# Power.net
KiCad netlist of a schematic drawn in Altium Designer
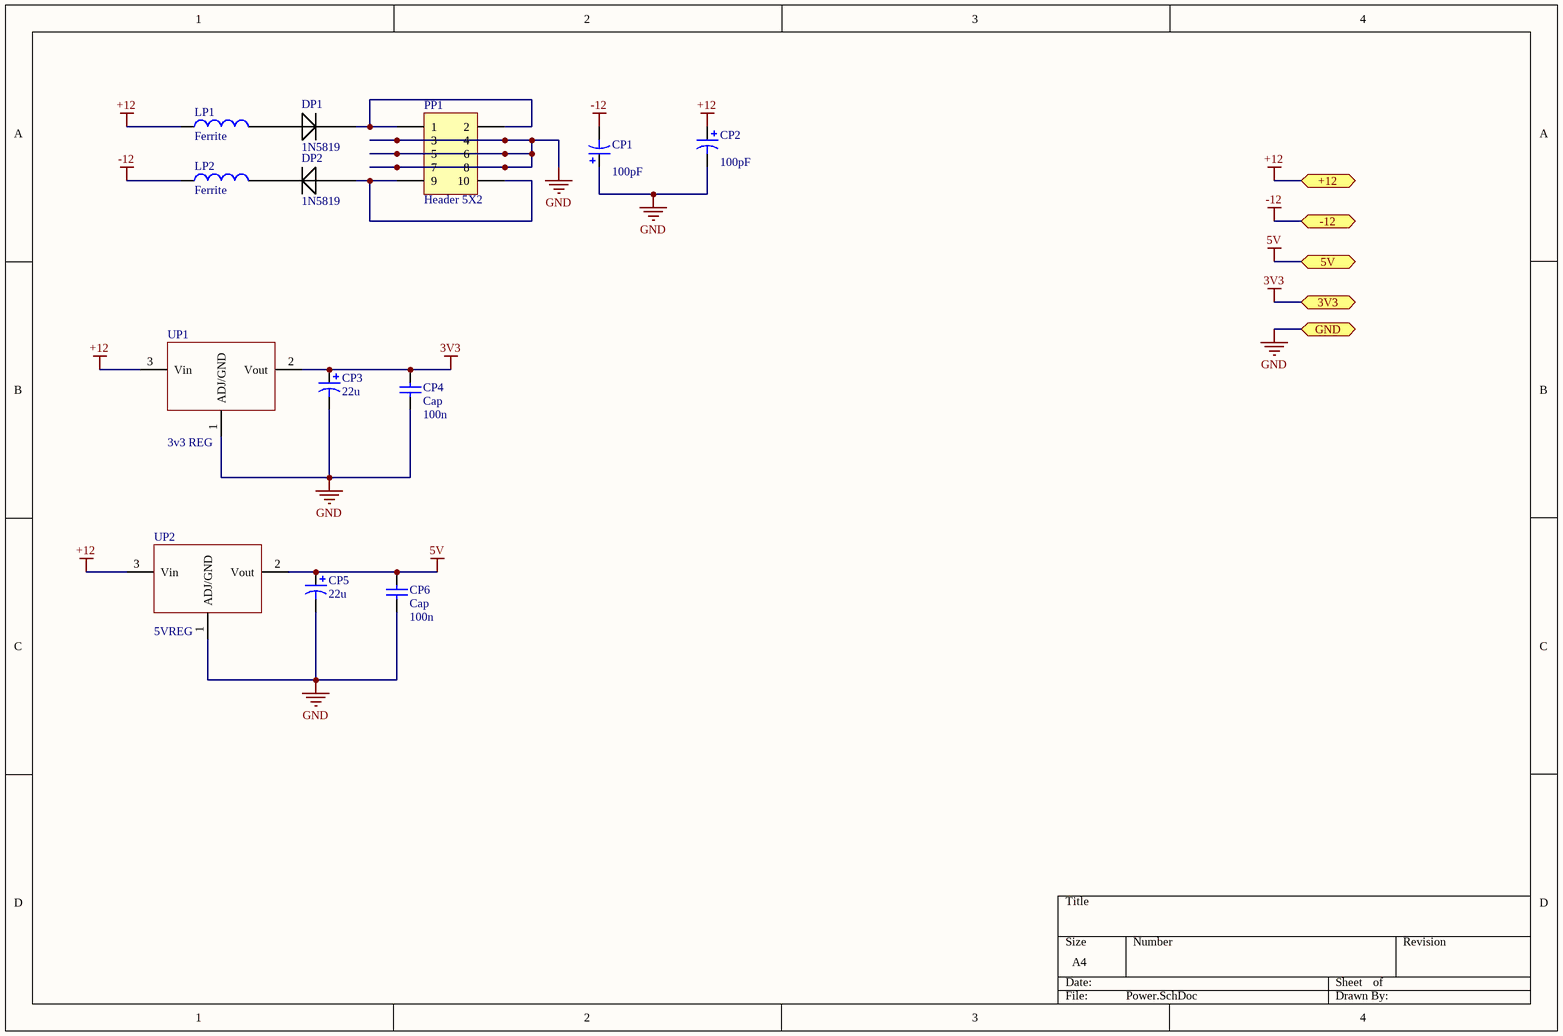
[diagram p0: Power.SchDoc]

(export (version "E")
  (design (tool "Eeschema 10.0.6"))
  (components
    (comp (ref "CP1")
      (value "100pF")
      (footprint "C-RAD-4.5")
      (description "Polarized Capacitor (Axial)")
      (fields (field (name "Comment") "Cap Pol2") (field (name "PUBLISHER") "Altium Limited"))
      (libsource (lib "Standard") (part "Cap Pol2"))
    )
    (comp (ref "CP2")
      (value "100pF")
      (footprint "C-RAD-4.5")
      (description "Polarized Capacitor (Axial)")
      (fields (field (name "Comment") "Cap Pol2") (field (name "PUBLISHER") "Altium Limited"))
      (libsource (lib "Standard") (part "Cap Pol2"))
    )
    (comp (ref "CP3")
      (value "22u")
      (footprint "C 0603 / 1608")
      (description "Polarized Capacitor (Axial)")
      (fields (field (name "Comment") "Cap Pol2") (field (name "PUBLISHER") "Altium Limited"))
      (libsource (lib "Standard") (part "Cap Pol2"))
    )
    (comp (ref "CP4")
      (value "Cap")
      (footprint "C 0603 / 1608")
      (description "Capacitor")
      (fields (field (name "ALTIUM_VALUE") "100n") (field (name "PUBLISHER") "Altium Limited"))
      (libsource (lib "Standard") (part "Cap"))
    )
    (comp (ref "CP5")
      (value "22u")
      (footprint "C 0603 / 1608")
      (description "Polarized Capacitor (Axial)")
      (fields (field (name "Comment") "Cap Pol2") (field (name "PUBLISHER") "Altium Limited"))
      (libsource (lib "Standard") (part "Cap Pol2"))
    )
    (comp (ref "CP6")
      (value "Cap")
      (footprint "C 0603 / 1608")
      (description "Capacitor")
      (fields (field (name "ALTIUM_VALUE") "100n") (field (name "PUBLISHER") "Altium Limited"))
      (libsource (lib "Standard") (part "Cap"))
    )
    (comp (ref "DP1") (value "1N5819") (footprint "DO-41") (libsource (lib "Standard") (part "Diode")))
    (comp (ref "DP2") (value "1N5819") (footprint "DO-41") (libsource (lib "Standard") (part "Diode")))
    (comp (ref "LP1")
      (value "Ferrite")
      (footprint "RES0805R")
      (fields (field (name "PUBLISHER") "Altium Limited"))
      (libsource (lib "Miscellaneous Devices") (part "Inductor"))
    )
    (comp (ref "LP2")
      (value "Ferrite")
      (footprint "RES0805R")
      (description "Inductor")
      (fields (field (name "PUBLISHER") "Altium Limited"))
      (libsource (lib "Miscellaneous Devices") (part "Inductor"))
    )
    (comp (ref "PP1")
      (value "Header 5X2")
      (footprint "HDR2X5")
      (description "Header, 5-Pin, Dual row")
      (fields (field (name "PUBLISHER") "Altium Limited"))
      (libsource (lib "Miscellaneous Connectors") (part "Header 5X2"))
    )
    (comp (ref "UP1")
      (value "3v3 REG")
      (footprint "SOT-223-3 - REG")
      (description "LDO 3.3V/5V/12V")
      (libsource (lib "IC") (part "AMS1117"))
    )
    (comp (ref "UP2")
      (value "5VREG")
      (footprint "SOT-223-3 - REG")
      (description "LDO 3.3V/5V/12V")
      (libsource (lib "IC") (part "AMS1117"))
    )
  )
  (nets
    (net (code "1") (name "+12") (class "Default")
      (node (ref "CP2") (pin "1") (pinfunction "1_1") (pintype "passive"))
      (node (ref "LP1") (pin "1") (pinfunction "1_1") (pintype "passive"))
      (node (ref "UP1") (pin "3") (pinfunction "Vin_3") (pintype "passive"))
      (node (ref "UP2") (pin "3") (pinfunction "Vin_3") (pintype "passive"))
    )
    (net (code "2") (name "-12") (class "Default")
      (node (ref "CP1") (pin "2") (pinfunction "2_2") (pintype "passive"))
      (node (ref "LP2") (pin "1") (pinfunction "1_1") (pintype "passive"))
    )
    (net (code "3") (name "3V3") (class "Default")
      (node (ref "CP3") (pin "1") (pinfunction "1_1") (pintype "passive"))
      (node (ref "CP4") (pin "2") (pinfunction "2_2") (pintype "passive"))
      (node (ref "UP1") (pin "2") (pinfunction "Vout_2") (pintype "passive"))
    )
    (net (code "4") (name "5V") (class "Default")
      (node (ref "CP5") (pin "1") (pinfunction "1_1") (pintype "passive"))
      (node (ref "CP6") (pin "2") (pinfunction "2_2") (pintype "passive"))
      (node (ref "UP2") (pin "2") (pinfunction "Vout_2") (pintype "passive"))
    )
    (net (code "5") (name "GND") (class "Default")
      (node (ref "CP1") (pin "1") (pinfunction "1_1") (pintype "passive"))
      (node (ref "CP2") (pin "2") (pinfunction "2_2") (pintype "passive"))
      (node (ref "CP3") (pin "2") (pinfunction "2_2") (pintype "passive"))
      (node (ref "CP4") (pin "1") (pinfunction "1_1") (pintype "passive"))
      (node (ref "CP5") (pin "2") (pinfunction "2_2") (pintype "passive"))
      (node (ref "CP6") (pin "1") (pinfunction "1_1") (pintype "passive"))
      (node (ref "PP1") (pin "3") (pinfunction "3_3") (pintype "passive"))
      (node (ref "PP1") (pin "4") (pinfunction "4_4") (pintype "passive"))
      (node (ref "PP1") (pin "5") (pinfunction "5_5") (pintype "passive"))
      (node (ref "PP1") (pin "6") (pinfunction "6_6") (pintype "passive"))
      (node (ref "PP1") (pin "7") (pinfunction "7_7") (pintype "passive"))
      (node (ref "PP1") (pin "8") (pinfunction "8_8") (pintype "passive"))
      (node (ref "UP1") (pin "1") (pinfunction "ADJ/GND_1") (pintype "passive"))
      (node (ref "UP2") (pin "1") (pinfunction "ADJ/GND_1") (pintype "passive"))
    )
    (net (code "6") (name "Net-(DP1-Pad1)") (class "Default")
      (node (ref "DP1") (pin "1") (pinfunction "1_1") (pintype "passive"))
      (node (ref "PP1") (pin "1") (pinfunction "1_1") (pintype "passive"))
      (node (ref "PP1") (pin "2") (pinfunction "2_2") (pintype "passive"))
    )
    (net (code "7") (name "Net-(DP1-Pad2)") (class "Default")
      (node (ref "DP1") (pin "2") (pinfunction "2_2") (pintype "passive"))
      (node (ref "LP1") (pin "2") (pinfunction "2_2") (pintype "passive"))
    )
    (net (code "8") (name "Net-(DP2-Pad1)") (class "Default")
      (node (ref "DP2") (pin "1") (pinfunction "1_1") (pintype "passive"))
      (node (ref "LP2") (pin "2") (pinfunction "2_2") (pintype "passive"))
    )
    (net (code "9") (name "Net-(DP2-Pad2)") (class "Default")
      (node (ref "DP2") (pin "2") (pinfunction "2_2") (pintype "passive"))
      (node (ref "PP1") (pin "10") (pinfunction "10_10") (pintype "passive"))
      (node (ref "PP1") (pin "9") (pinfunction "9_9") (pintype "passive"))
    )
  )
)
